# 1-Half_Bridge.net
KiCad netlist of a schematic drawn in Altium Designer
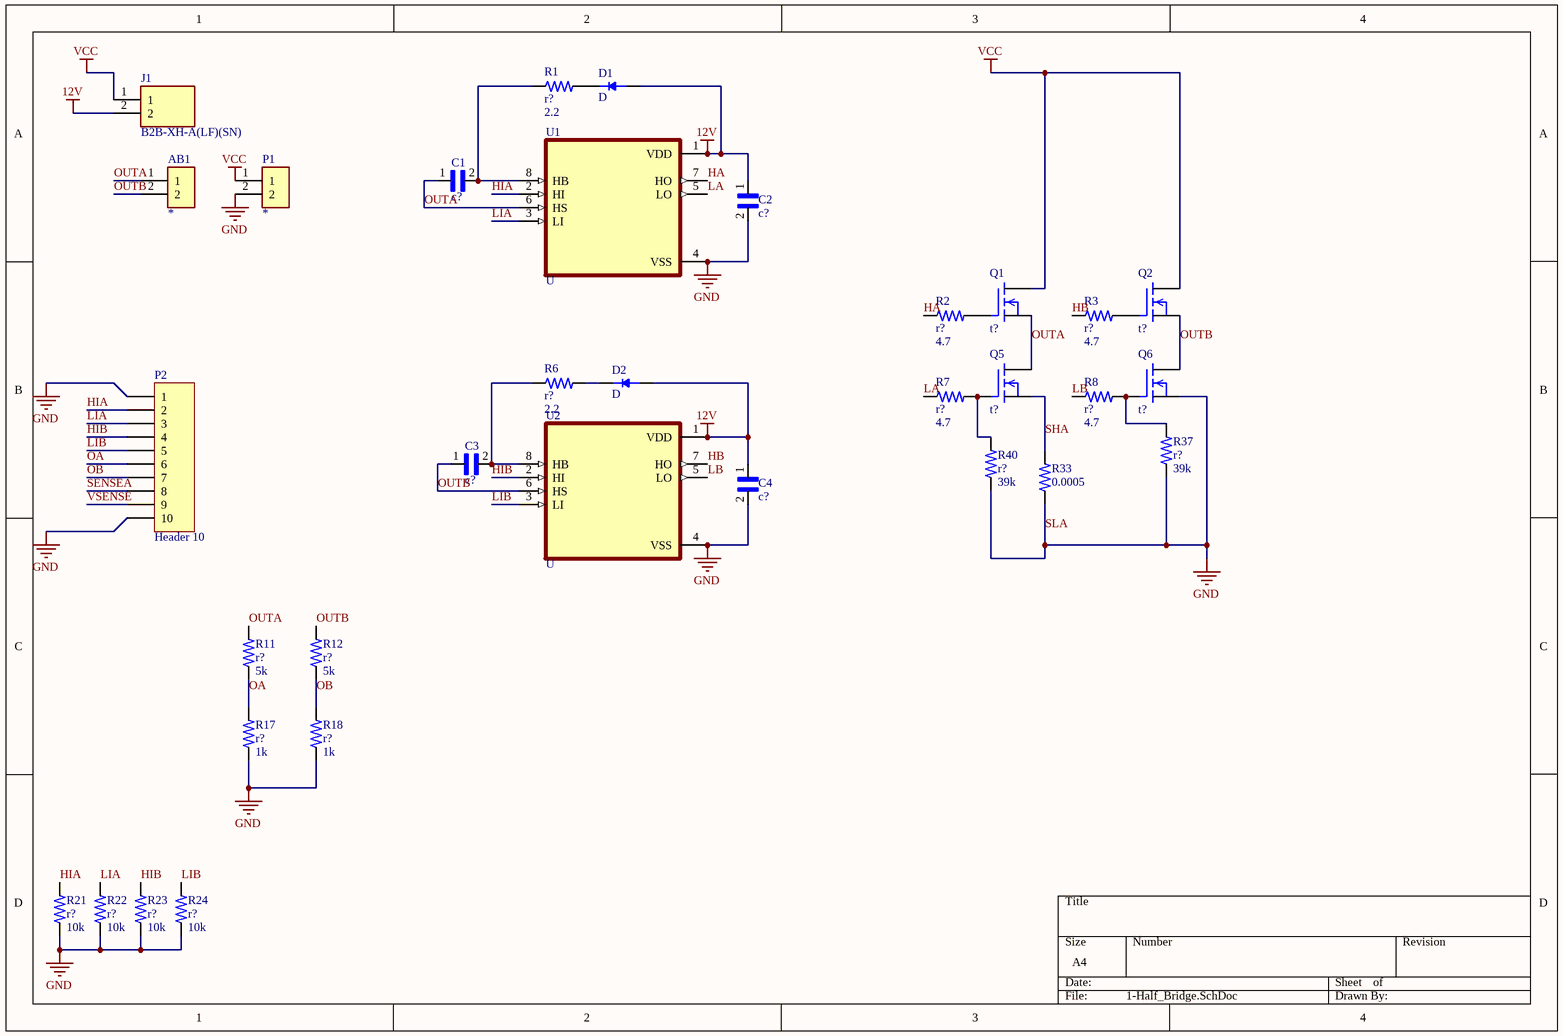
[diagram p0: 1-Half_Bridge.SchDoc]

(export (version "E")
  (design (tool "Eeschema 10.0.6"))
  (components
    (comp (ref "AB1")
      (value "282837-2")
      (footprint "terminal")
      (description "Connector Terminal Blocks Receptacle 2 Position 5.08mm Solder Straight Thru-Hole 13.5A/Contact")
      (fields
        (field (name "MF") "TE Connectivity")
        (field (name "DIGI-KEY_PART_NUMBER") "A113320-ND")
        (field (name "COMMENT_1") "*")
      )
      (libsource (lib "iresh_Integrated_Library") (part "terminal 2"))
    )
    (comp (ref "C1")
      (value "c?")
      (footprint "cap 1206")
      (description "Film Capacitor")
      (fields (field (name "MP") "CB018B0103JBA") (field (name "MF") "AVX"))
      (libsource (lib "iresh_Integrated_Library") (part "Cap 1206"))
    )
    (comp (ref "C2")
      (value "c?")
      (footprint "cap 1206")
      (description "Film Capacitor")
      (fields (field (name "MP") "CB018B0103JBA") (field (name "MF") "AVX"))
      (libsource (lib "") (part "Cap 1206_1"))
    )
    (comp (ref "C3")
      (value "c?")
      (footprint "cap 1206")
      (description "Film Capacitor")
      (fields (field (name "MP") "CB018B0103JBA") (field (name "MF") "AVX"))
      (libsource (lib "iresh_Integrated_Library") (part "Cap 1206"))
    )
    (comp (ref "C4")
      (value "c?")
      (footprint "cap 1206")
      (description "Film Capacitor")
      (fields (field (name "MP") "CB018B0103JBA") (field (name "MF") "AVX"))
      (libsource (lib "") (part "Cap 1206_1"))
    )
    (comp (ref "D1")
      (value "D")
      (footprint "do 214")
      (description "Diode Schottky 30V 100mA Surface Mount GMD2")
      (fields (field (name "MP") "RB520ZS-30T2R") (field (name "MF") "Rohm"))
      (libsource (lib "iresh_Integrated_Library") (part "mura110"))
    )
    (comp (ref "D2")
      (value "D")
      (footprint "do 214")
      (description "Diode Schottky 30V 100mA Surface Mount GMD2")
      (fields (field (name "MP") "RB520ZS-30T2R") (field (name "MF") "Rohm"))
      (libsource (lib "iresh_Integrated_Library") (part "mura110"))
    )
    (comp (ref "J1")
      (value "B2B-XH-A(LF)(SN)")
      (footprint "JST_B2B-XH-A(LF)(SN)")
      (description "Connector Header Through Hole 2 position 0.098 _2.50mm_")
      (fields (field (name "MP") "B2B-XH-A_LF__SN_") (field (name "MF") "JST Sales"))
      (libsource (lib "iresh_Integrated_Library") (part "B2B-XH-A(LF)(SN)"))
    )
    (comp (ref "P1")
      (value "282837-2")
      (footprint "terminal")
      (description "Connector Terminal Blocks Receptacle 2 Position 5.08mm Solder Straight Thru-Hole 13.5A/Contact")
      (fields
        (field (name "MF") "TE Connectivity")
        (field (name "DIGI-KEY_PART_NUMBER") "A113320-ND")
        (field (name "COMMENT_1") "*")
      )
      (libsource (lib "iresh_Integrated_Library") (part "terminal 2"))
    )
    (comp (ref "P2")
      (value "Header 10")
      (footprint "HDR1X10")
      (description "Header, 10-Pin")
      (fields (field (name "PUBLISHER") "Altium Limited"))
      (libsource (lib "Miscellaneous Connectors") (part "Header 10"))
    )
    (comp (ref "Q1")
      (value "t?")
      (footprint "TO-263AB")
      (description "N-Channel 60V 200mA _Ta_ 350mW _Tc_ Through Hole TO-92-3")
      (fields (field (name "MF") "ON Semiconductor") (field (name "MP") "2N7000G"))
      (libsource (lib "iresh_Integrated_Library") (part "n-mos"))
    )
    (comp (ref "Q2")
      (value "t?")
      (footprint "TO-263AB")
      (description "N-Channel 60V 200mA _Ta_ 350mW _Tc_ Through Hole TO-92-3")
      (fields (field (name "MF") "ON Semiconductor") (field (name "MP") "2N7000G"))
      (libsource (lib "iresh_Integrated_Library") (part "n-mos"))
    )
    (comp (ref "Q5")
      (value "t?")
      (footprint "TO-263AB")
      (description "N-Channel 60V 200mA _Ta_ 350mW _Tc_ Through Hole TO-92-3")
      (fields (field (name "MF") "ON Semiconductor") (field (name "MP") "2N7000G"))
      (libsource (lib "iresh_Integrated_Library") (part "n-mos"))
    )
    (comp (ref "Q6")
      (value "t?")
      (footprint "TO-263AB")
      (description "N-Channel 60V 200mA _Ta_ 350mW _Tc_ Through Hole TO-92-3")
      (fields (field (name "MF") "ON Semiconductor") (field (name "MP") "2N7000G"))
      (libsource (lib "iresh_Integrated_Library") (part "n-mos"))
    )
    (comp (ref "R1")
      (value "r?")
      (footprint "RES-0805")
      (description "Res, Thin Film, 16r5, 0.1%, 0.25w, 0805")
      (fields
        (field (name "MP") "RP73PF2A16R5BTDF")
        (field (name "MF") "TE Connectivity")
        (field (name "ALTIUM_VALUE") "2.2")
      )
      (libsource (lib "iresh_Integrated_Library") (part "Res-0805"))
    )
    (comp (ref "R2")
      (value "r?")
      (footprint "RES-0805")
      (description "Res, Thin Film, 16r5, 0.1%, 0.25w, 0805")
      (fields
        (field (name "MP") "RP73PF2A16R5BTDF")
        (field (name "MF") "TE Connectivity")
        (field (name "ALTIUM_VALUE") "4.7")
      )
      (libsource (lib "iresh_Integrated_Library") (part "Res-0805"))
    )
    (comp (ref "R3")
      (value "r?")
      (footprint "RES-0805")
      (description "Res, Thin Film, 16r5, 0.1%, 0.25w, 0805")
      (fields
        (field (name "MP") "RP73PF2A16R5BTDF")
        (field (name "MF") "TE Connectivity")
        (field (name "ALTIUM_VALUE") "4.7")
      )
      (libsource (lib "iresh_Integrated_Library") (part "Res-0805"))
    )
    (comp (ref "R6")
      (value "r?")
      (footprint "RES-0805")
      (description "Res, Thin Film, 16r5, 0.1%, 0.25w, 0805")
      (fields
        (field (name "MP") "RP73PF2A16R5BTDF")
        (field (name "MF") "TE Connectivity")
        (field (name "ALTIUM_VALUE") "2.2")
      )
      (libsource (lib "iresh_Integrated_Library") (part "Res-0805"))
    )
    (comp (ref "R7")
      (value "r?")
      (footprint "RES-0805")
      (description "Res, Thin Film, 16r5, 0.1%, 0.25w, 0805")
      (fields
        (field (name "MP") "RP73PF2A16R5BTDF")
        (field (name "MF") "TE Connectivity")
        (field (name "ALTIUM_VALUE") "4.7")
      )
      (libsource (lib "iresh_Integrated_Library") (part "Res-0805"))
    )
    (comp (ref "R8")
      (value "r?")
      (footprint "RES-0805")
      (description "Res, Thin Film, 16r5, 0.1%, 0.25w, 0805")
      (fields
        (field (name "MP") "RP73PF2A16R5BTDF")
        (field (name "MF") "TE Connectivity")
        (field (name "ALTIUM_VALUE") "4.7")
      )
      (libsource (lib "iresh_Integrated_Library") (part "Res-0805"))
    )
    (comp (ref "R11")
      (value "r?")
      (footprint "RES-0805")
      (description "Res, Thin Film, 16r5, 0.1%, 0.25w, 0805")
      (fields
        (field (name "MP") "RP73PF2A16R5BTDF")
        (field (name "MF") "TE Connectivity")
        (field (name "ALTIUM_VALUE") "5k")
      )
      (libsource (lib "iresh_Integrated_Library") (part "Res-0805"))
    )
    (comp (ref "R12")
      (value "r?")
      (footprint "RES-0805")
      (description "Res, Thin Film, 16r5, 0.1%, 0.25w, 0805")
      (fields
        (field (name "MP") "RP73PF2A16R5BTDF")
        (field (name "MF") "TE Connectivity")
        (field (name "ALTIUM_VALUE") "5k")
      )
      (libsource (lib "iresh_Integrated_Library") (part "Res-0805"))
    )
    (comp (ref "R17")
      (value "r?")
      (footprint "RES-0805")
      (description "Res, Thin Film, 16r5, 0.1%, 0.25w, 0805")
      (fields
        (field (name "MP") "RP73PF2A16R5BTDF")
        (field (name "MF") "TE Connectivity")
        (field (name "ALTIUM_VALUE") "1k")
      )
      (libsource (lib "iresh_Integrated_Library") (part "Res-0805"))
    )
    (comp (ref "R18")
      (value "r?")
      (footprint "RES-0805")
      (description "Res, Thin Film, 16r5, 0.1%, 0.25w, 0805")
      (fields
        (field (name "MP") "RP73PF2A16R5BTDF")
        (field (name "MF") "TE Connectivity")
        (field (name "ALTIUM_VALUE") "1k")
      )
      (libsource (lib "iresh_Integrated_Library") (part "Res-0805"))
    )
    (comp (ref "R21")
      (value "r?")
      (footprint "RES-0805")
      (description "Res, Thin Film, 16r5, 0.1%, 0.25w, 0805")
      (fields
        (field (name "MP") "RP73PF2A16R5BTDF")
        (field (name "MF") "TE Connectivity")
        (field (name "ALTIUM_VALUE") "10k")
      )
      (libsource (lib "iresh_Integrated_Library") (part "Res-0805"))
    )
    (comp (ref "R22")
      (value "r?")
      (footprint "RES-0805")
      (description "Res, Thin Film, 16r5, 0.1%, 0.25w, 0805")
      (fields
        (field (name "MP") "RP73PF2A16R5BTDF")
        (field (name "MF") "TE Connectivity")
        (field (name "ALTIUM_VALUE") "10k")
      )
      (libsource (lib "iresh_Integrated_Library") (part "Res-0805"))
    )
    (comp (ref "R23")
      (value "r?")
      (footprint "RES-0805")
      (description "Res, Thin Film, 16r5, 0.1%, 0.25w, 0805")
      (fields
        (field (name "MP") "RP73PF2A16R5BTDF")
        (field (name "MF") "TE Connectivity")
        (field (name "ALTIUM_VALUE") "10k")
      )
      (libsource (lib "iresh_Integrated_Library") (part "Res-0805"))
    )
    (comp (ref "R24")
      (value "r?")
      (footprint "RES-0805")
      (description "Res, Thin Film, 16r5, 0.1%, 0.25w, 0805")
      (fields
        (field (name "MP") "RP73PF2A16R5BTDF")
        (field (name "MF") "TE Connectivity")
        (field (name "ALTIUM_VALUE") "10k")
      )
      (libsource (lib "iresh_Integrated_Library") (part "Res-0805"))
    )
    (comp (ref "R33")
      (value "0.0005")
      (footprint "2512")
      (description "TLR 2512 2.0W R006 1% 50PPM 2K RL")
      (fields (field (name "TOLERANCE") "1%") (field (name "MP") "TLR3A20DR006FTDG"))
      (libsource (lib "ire_int") (part "RES-2512"))
    )
    (comp (ref "R37")
      (value "r?")
      (footprint "RES-0805")
      (description "Res, Thin Film, 16r5, 0.1%, 0.25w, 0805")
      (fields
        (field (name "MP") "RP73PF2A16R5BTDF")
        (field (name "MF") "TE Connectivity")
        (field (name "ALTIUM_VALUE") "39k")
      )
      (libsource (lib "iresh_Integrated_Library") (part "Res-0805"))
    )
    (comp (ref "R40")
      (value "r?")
      (footprint "RES-0805")
      (description "Res, Thin Film, 16r5, 0.1%, 0.25w, 0805")
      (fields
        (field (name "MP") "RP73PF2A16R5BTDF")
        (field (name "MF") "TE Connectivity")
        (field (name "ALTIUM_VALUE") "39k")
      )
      (libsource (lib "iresh_Integrated_Library") (part "Res-0805"))
    )
    (comp (ref "U1")
      (value "U")
      (footprint "SOIC 8N")
      (description "1-A, 100-V half bridge gate driver with 8-V UVLO and high noise immunity 8-SOIC -40 to 125")
      (fields (field (name "MF") "Texas Instruments") (field (name "MP") "LM5109BMA"))
      (libsource (lib "iresh_Integrated_Library") (part "LM5109BMA"))
    )
    (comp (ref "U2")
      (value "U")
      (footprint "SOIC 8N")
      (description "1-A, 100-V half bridge gate driver with 8-V UVLO and high noise immunity 8-SOIC -40 to 125")
      (fields (field (name "MF") "Texas Instruments") (field (name "MP") "LM5109BMA"))
      (libsource (lib "iresh_Integrated_Library") (part "LM5109BMA"))
    )
  )
  (nets
    (net (code "1") (name "/HA") (class "Default")
      (node (ref "R2") (pin "1") (pinfunction "1_1") (pintype "passive"))
      (node (ref "U1") (pin "7") (pinfunction "HO_7") (pintype "output"))
    )
    (net (code "2") (name "/HB") (class "Default")
      (node (ref "R3") (pin "1") (pinfunction "1_1") (pintype "passive"))
      (node (ref "U2") (pin "7") (pinfunction "HO_7") (pintype "output"))
    )
    (net (code "3") (name "/HIA") (class "Default")
      (node (ref "P2") (pin "2") (pinfunction "2_2") (pintype "passive"))
      (node (ref "R21") (pin "2") (pinfunction "2_2") (pintype "passive"))
      (node (ref "U1") (pin "2") (pinfunction "HI_2") (pintype "input"))
    )
    (net (code "4") (name "/HIB") (class "Default")
      (node (ref "P2") (pin "4") (pinfunction "4_4") (pintype "passive"))
      (node (ref "R23") (pin "2") (pinfunction "2_2") (pintype "passive"))
      (node (ref "U2") (pin "2") (pinfunction "HI_2") (pintype "input"))
    )
    (net (code "5") (name "/LA") (class "Default")
      (node (ref "R7") (pin "1") (pinfunction "1_1") (pintype "passive"))
      (node (ref "U1") (pin "5") (pinfunction "LO_5") (pintype "output"))
    )
    (net (code "6") (name "/LB") (class "Default")
      (node (ref "R8") (pin "1") (pinfunction "1_1") (pintype "passive"))
      (node (ref "U2") (pin "5") (pinfunction "LO_5") (pintype "output"))
    )
    (net (code "7") (name "/LIA") (class "Default")
      (node (ref "P2") (pin "3") (pinfunction "3_3") (pintype "passive"))
      (node (ref "R22") (pin "2") (pinfunction "2_2") (pintype "passive"))
      (node (ref "U1") (pin "3") (pinfunction "LI_3") (pintype "input"))
    )
    (net (code "8") (name "/LIB") (class "Default")
      (node (ref "P2") (pin "5") (pinfunction "5_5") (pintype "passive"))
      (node (ref "R24") (pin "2") (pinfunction "2_2") (pintype "passive"))
      (node (ref "U2") (pin "3") (pinfunction "LI_3") (pintype "input"))
    )
    (net (code "9") (name "/OA") (class "Default")
      (node (ref "P2") (pin "6") (pinfunction "6_6") (pintype "passive"))
      (node (ref "R11") (pin "1") (pinfunction "1_1") (pintype "passive"))
      (node (ref "R17") (pin "2") (pinfunction "2_2") (pintype "passive"))
    )
    (net (code "10") (name "/OB") (class "Default")
      (node (ref "P2") (pin "7") (pinfunction "7_7") (pintype "passive"))
      (node (ref "R12") (pin "1") (pinfunction "1_1") (pintype "passive"))
      (node (ref "R18") (pin "2") (pinfunction "2_2") (pintype "passive"))
    )
    (net (code "11") (name "/OUTA") (class "Default")
      (node (ref "AB1") (pin "1") (pinfunction "1_1") (pintype "passive"))
      (node (ref "C1") (pin "1") (pinfunction "1_1") (pintype "passive"))
      (node (ref "Q1") (pin "1") (pinfunction "SRC_1") (pintype "passive"))
      (node (ref "Q5") (pin "3") (pinfunction "DRN_3") (pintype "passive"))
      (node (ref "R11") (pin "2") (pinfunction "2_2") (pintype "passive"))
      (node (ref "U1") (pin "6") (pinfunction "HS_6") (pintype "input"))
    )
    (net (code "12") (name "/OUTB") (class "Default")
      (node (ref "AB1") (pin "2") (pinfunction "2_2") (pintype "passive"))
      (node (ref "C3") (pin "1") (pinfunction "1_1") (pintype "passive"))
      (node (ref "Q2") (pin "1") (pinfunction "SRC_1") (pintype "passive"))
      (node (ref "Q6") (pin "3") (pinfunction "DRN_3") (pintype "passive"))
      (node (ref "R12") (pin "2") (pinfunction "2_2") (pintype "passive"))
      (node (ref "U2") (pin "6") (pinfunction "HS_6") (pintype "input"))
    )
    (net (code "13") (name "/SENSEA") (class "Default")
      (node (ref "P2") (pin "8") (pinfunction "8_8") (pintype "passive"))
    )
    (net (code "14") (name "/SHA") (class "Default")
      (node (ref "Q5") (pin "1") (pinfunction "SRC_1") (pintype "passive"))
      (node (ref "R33") (pin "2") (pinfunction "2_2") (pintype "passive"))
    )
    (net (code "15") (name "/VSENSE") (class "Default")
      (node (ref "P2") (pin "9") (pinfunction "9_9") (pintype "passive"))
    )
    (net (code "16") (name "12V") (class "Default")
      (node (ref "C2") (pin "1") (pinfunction "1_1") (pintype "passive"))
      (node (ref "C4") (pin "1") (pinfunction "1_1") (pintype "passive"))
      (node (ref "D1") (pin "A") (pinfunction "A_A") (pintype "passive"))
      (node (ref "D2") (pin "A") (pinfunction "A_A") (pintype "passive"))
      (node (ref "J1") (pin "2") (pinfunction "2_2") (pintype "passive"))
      (node (ref "U1") (pin "1") (pinfunction "VDD_1") (pintype "power_in"))
      (node (ref "U2") (pin "1") (pinfunction "VDD_1") (pintype "power_in"))
    )
    (net (code "17") (name "GND") (class "Default")
      (node (ref "C2") (pin "2") (pinfunction "2_2") (pintype "passive"))
      (node (ref "C4") (pin "2") (pinfunction "2_2") (pintype "passive"))
      (node (ref "P1") (pin "2") (pinfunction "2_2") (pintype "passive"))
      (node (ref "P2") (pin "1") (pinfunction "1_1") (pintype "passive"))
      (node (ref "P2") (pin "10") (pinfunction "10_10") (pintype "passive"))
      (node (ref "Q6") (pin "1") (pinfunction "SRC_1") (pintype "passive"))
      (node (ref "R17") (pin "1") (pinfunction "1_1") (pintype "passive"))
      (node (ref "R18") (pin "1") (pinfunction "1_1") (pintype "passive"))
      (node (ref "R21") (pin "1") (pinfunction "1_1") (pintype "passive"))
      (node (ref "R22") (pin "1") (pinfunction "1_1") (pintype "passive"))
      (node (ref "R23") (pin "1") (pinfunction "1_1") (pintype "passive"))
      (node (ref "R24") (pin "1") (pinfunction "1_1") (pintype "passive"))
      (node (ref "R33") (pin "1") (pinfunction "1_1") (pintype "passive"))
      (node (ref "R37") (pin "1") (pinfunction "1_1") (pintype "passive"))
      (node (ref "R40") (pin "1") (pinfunction "1_1") (pintype "passive"))
      (node (ref "U1") (pin "4") (pinfunction "VSS_4") (pintype "power_in"))
      (node (ref "U2") (pin "4") (pinfunction "VSS_4") (pintype "power_in"))
    )
    (net (code "18") (name "Net-(D1-PadC)") (class "Default")
      (node (ref "D1") (pin "C") (pinfunction "C_C") (pintype "passive"))
      (node (ref "R1") (pin "2") (pinfunction "2_2") (pintype "passive"))
    )
    (net (code "19") (name "Net-(D2-PadC)") (class "Default")
      (node (ref "D2") (pin "C") (pinfunction "C_C") (pintype "passive"))
      (node (ref "R6") (pin "2") (pinfunction "2_2") (pintype "passive"))
    )
    (net (code "20") (name "Net-(Q1-GATE)") (class "Default")
      (node (ref "Q1") (pin "2") (pinfunction "GATE_2") (pintype "passive"))
      (node (ref "R2") (pin "2") (pinfunction "2_2") (pintype "passive"))
    )
    (net (code "21") (name "Net-(Q2-GATE)") (class "Default")
      (node (ref "Q2") (pin "2") (pinfunction "GATE_2") (pintype "passive"))
      (node (ref "R3") (pin "2") (pinfunction "2_2") (pintype "passive"))
    )
    (net (code "22") (name "Net-(Q5-GATE)") (class "Default")
      (node (ref "Q5") (pin "2") (pinfunction "GATE_2") (pintype "passive"))
      (node (ref "R40") (pin "2") (pinfunction "2_2") (pintype "passive"))
      (node (ref "R7") (pin "2") (pinfunction "2_2") (pintype "passive"))
    )
    (net (code "23") (name "Net-(Q6-GATE)") (class "Default")
      (node (ref "Q6") (pin "2") (pinfunction "GATE_2") (pintype "passive"))
      (node (ref "R37") (pin "2") (pinfunction "2_2") (pintype "passive"))
      (node (ref "R8") (pin "2") (pinfunction "2_2") (pintype "passive"))
    )
    (net (code "24") (name "Net-(U1-HB)") (class "Default")
      (node (ref "C1") (pin "2") (pinfunction "2_2") (pintype "passive"))
      (node (ref "R1") (pin "1") (pinfunction "1_1") (pintype "passive"))
      (node (ref "U1") (pin "8") (pinfunction "HB_8") (pintype "input"))
    )
    (net (code "25") (name "Net-(U2-HB)") (class "Default")
      (node (ref "C3") (pin "2") (pinfunction "2_2") (pintype "passive"))
      (node (ref "R6") (pin "1") (pinfunction "1_1") (pintype "passive"))
      (node (ref "U2") (pin "8") (pinfunction "HB_8") (pintype "input"))
    )
    (net (code "26") (name "VCC") (class "Default")
      (node (ref "J1") (pin "1") (pinfunction "1_1") (pintype "passive"))
      (node (ref "P1") (pin "1") (pinfunction "1_1") (pintype "passive"))
      (node (ref "Q1") (pin "3") (pinfunction "DRN_3") (pintype "passive"))
      (node (ref "Q2") (pin "3") (pinfunction "DRN_3") (pintype "passive"))
    )
  )
)
